# DI_DO.net
KiCad netlist of a schematic drawn in Altium Designer
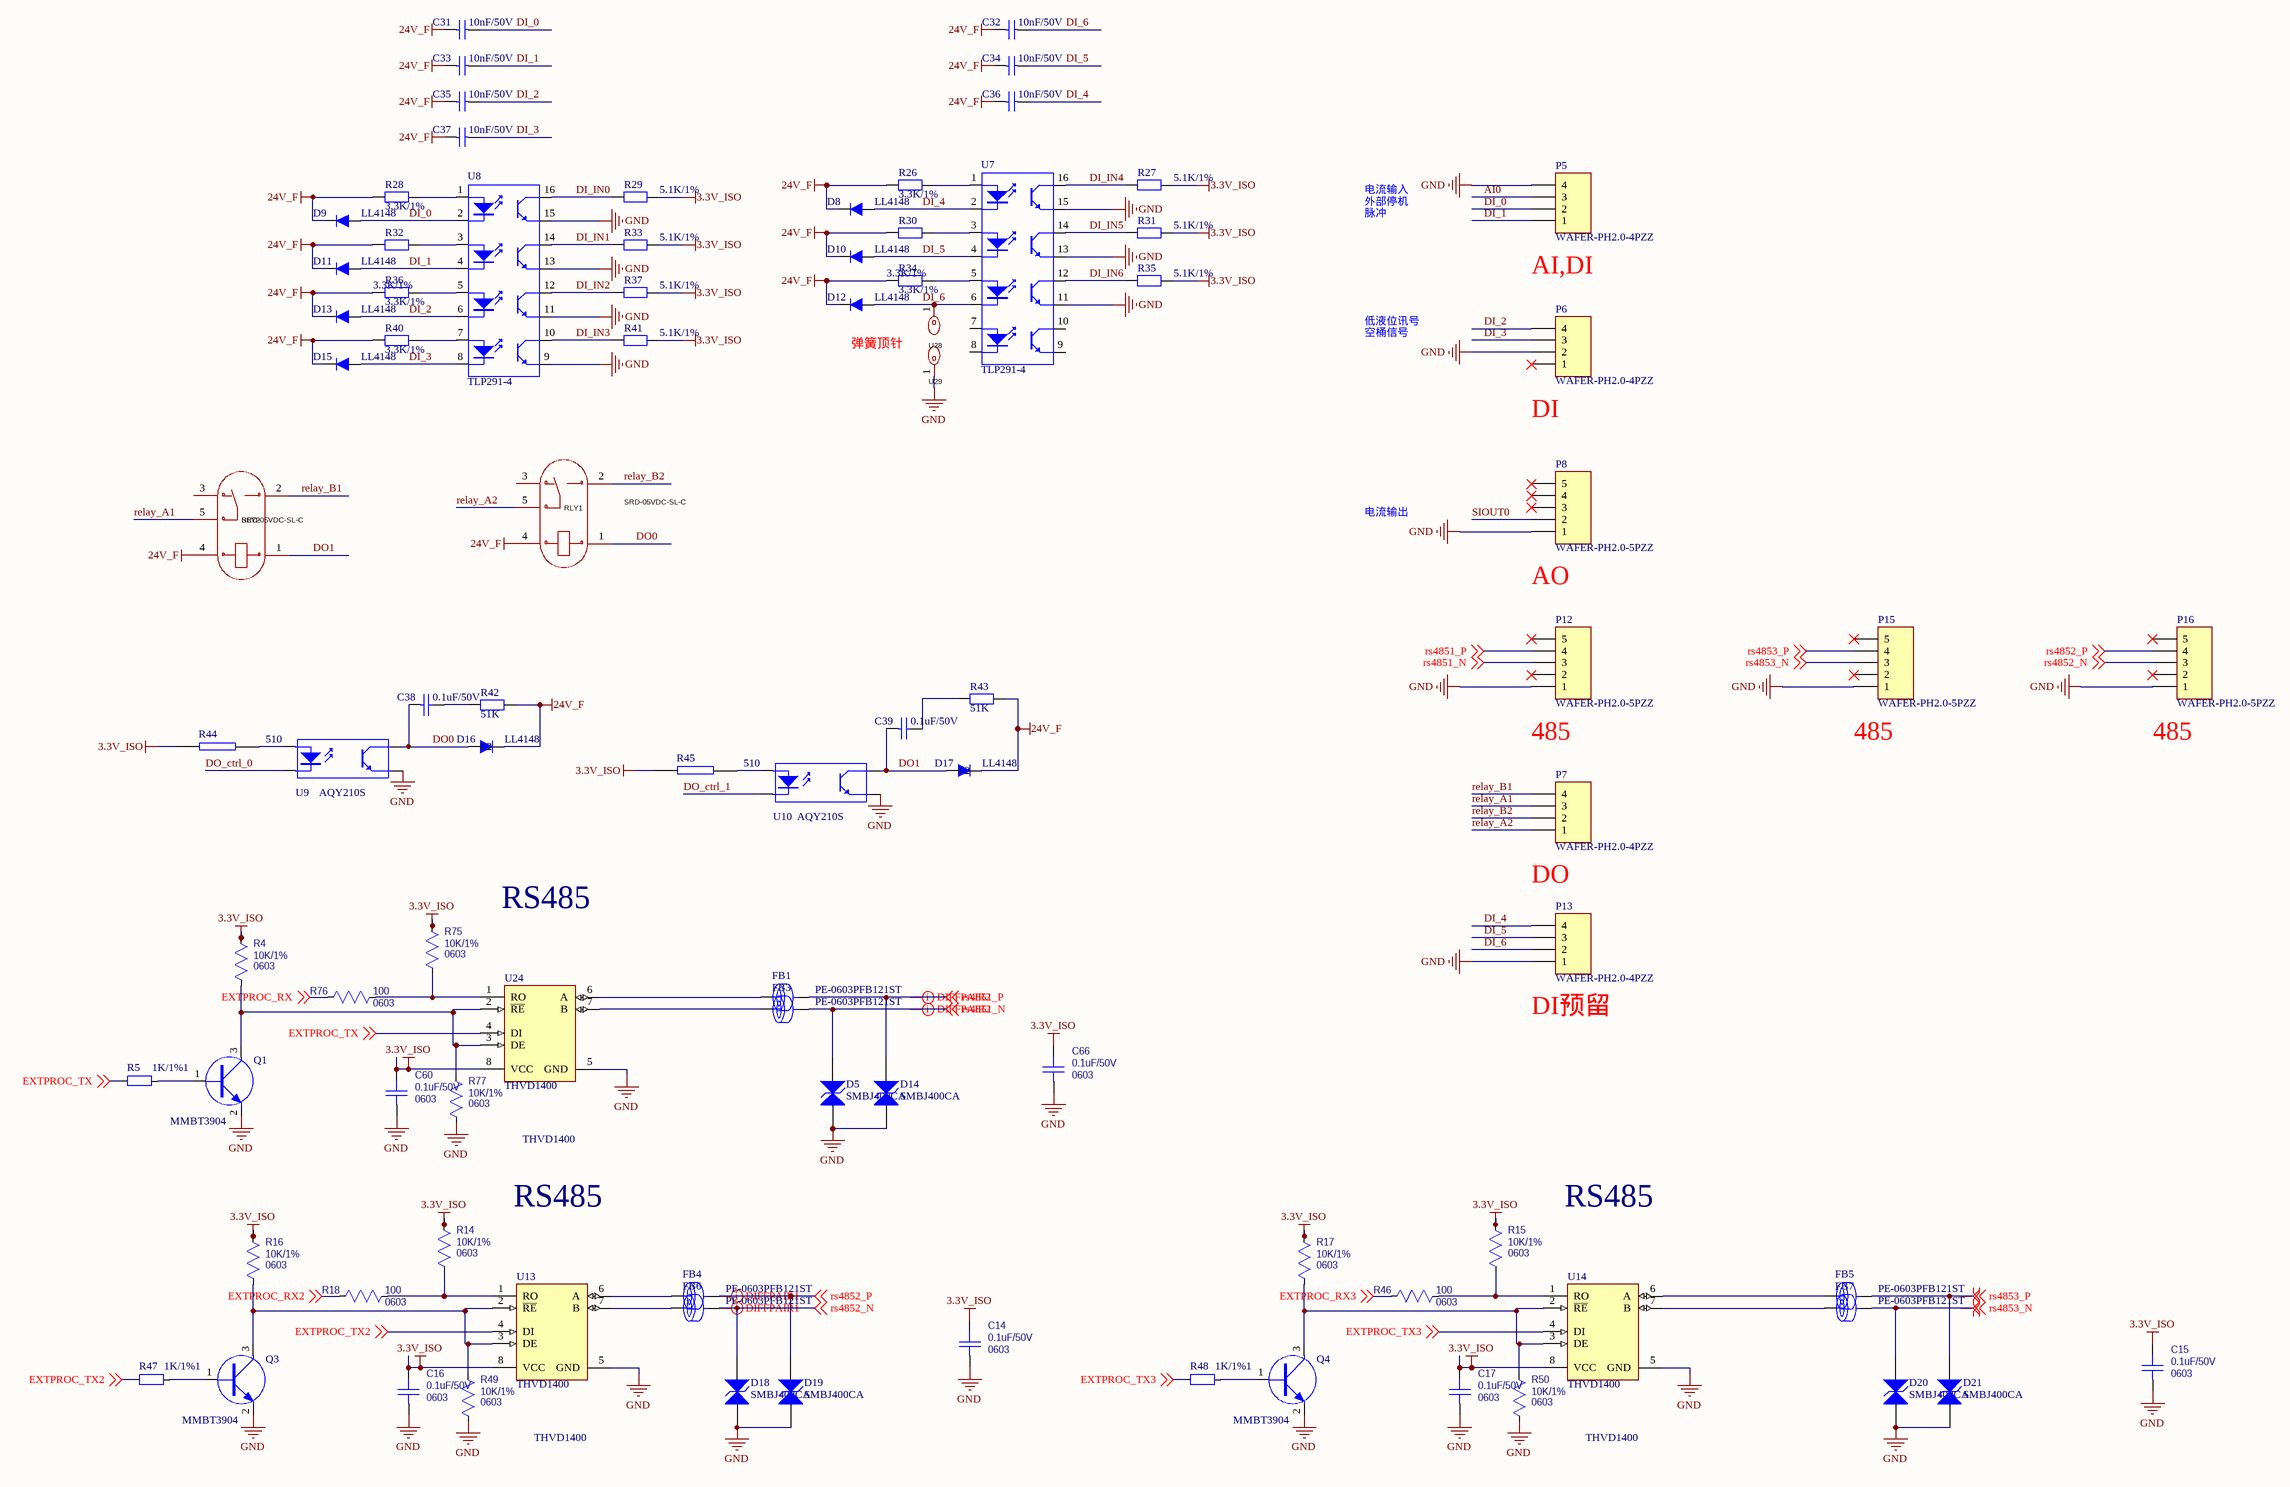
[diagram p0: DI_DO.SchDoc]

(export (version "E")
  (design (tool "Eeschema 10.0.6"))
  (components
    (comp (ref "C14")
      (value "0.1uF/50V")
      (footprint "0603C")
      (description "Capacitor, MLCC")
      (fields (field (name "PACKAGE") "0603"))
      (libsource (lib "Karl") (part "Capacitor_0603"))
    )
    (comp (ref "C15")
      (value "0.1uF/50V")
      (footprint "0603C")
      (description "Capacitor, MLCC")
      (fields (field (name "PACKAGE") "0603"))
      (libsource (lib "Karl") (part "Capacitor_0603"))
    )
    (comp (ref "C16")
      (value "0.1uF/50V")
      (footprint "0603C")
      (description "Capacitor, MLCC")
      (fields (field (name "PACKAGE") "0603"))
      (libsource (lib "Karl") (part "Capacitor_0603"))
    )
    (comp (ref "C17")
      (value "0.1uF/50V")
      (footprint "0603C")
      (description "Capacitor, MLCC")
      (fields (field (name "PACKAGE") "0603"))
      (libsource (lib "Karl") (part "Capacitor_0603"))
    )
    (comp (ref "C31")
      (value "10nF/50V")
      (footprint "0603C")
      (description "Capacitor")
      (libsource (lib "Miscellaneous Devices") (part "Cap"))
    )
    (comp (ref "C32")
      (value "10nF/50V")
      (footprint "0603C")
      (description "Capacitor")
      (libsource (lib "Miscellaneous Devices") (part "Cap"))
    )
    (comp (ref "C33")
      (value "10nF/50V")
      (footprint "0603C")
      (description "Capacitor")
      (libsource (lib "Miscellaneous Devices") (part "Cap"))
    )
    (comp (ref "C34")
      (value "10nF/50V")
      (footprint "0603C")
      (description "Capacitor")
      (libsource (lib "Miscellaneous Devices") (part "Cap"))
    )
    (comp (ref "C35")
      (value "10nF/50V")
      (footprint "0603C")
      (description "Capacitor")
      (libsource (lib "Miscellaneous Devices") (part "Cap"))
    )
    (comp (ref "C36")
      (value "10nF/50V")
      (footprint "0603C")
      (description "Capacitor")
      (libsource (lib "Miscellaneous Devices") (part "Cap"))
    )
    (comp (ref "C37")
      (value "10nF/50V")
      (footprint "0603C")
      (description "Capacitor")
      (libsource (lib "Miscellaneous Devices") (part "Cap"))
    )
    (comp (ref "C38")
      (value "0.1uF/50V")
      (footprint "0603C")
      (description "Capacitor")
      (libsource (lib "*") (part "CAP"))
    )
    (comp (ref "C39")
      (value "0.1uF/50V")
      (footprint "0603C")
      (description "Capacitor")
      (libsource (lib "*") (part "CAP"))
    )
    (comp (ref "C60")
      (value "0.1uF/50V")
      (footprint "0603C")
      (description "Capacitor, MLCC")
      (fields (field (name "PACKAGE") "0603"))
      (libsource (lib "Karl") (part "Capacitor_0603"))
    )
    (comp (ref "C66")
      (value "0.1uF/50V")
      (footprint "0603C")
      (description "Capacitor, MLCC")
      (fields (field (name "PACKAGE") "0603"))
      (libsource (lib "Karl") (part "Capacitor_0603"))
    )
    (comp (ref "D5")
      (value "SMBJ400CA")
      (footprint "SMB")
      (description "Transient Voltage Suppression Diode, 400 W, 33 V, -65 to 150 degC, 2-Pin SMD, RoHS, Tape and Reel")
      (libsource (lib "Bogen") (part "SMAJ12CA"))
    )
    (comp (ref "D8")
      (value "LL4148")
      (footprint "DO-213AB/LL34/MiniMELF")
      (description "VISHAY,LL4148,圆柱体MiniMELF100V/2A,ROHS")
      (libsource (lib "Device2018") (part "LL4148"))
    )
    (comp (ref "D9")
      (value "LL4148")
      (footprint "DO-213AB/LL34/MiniMELF")
      (description "VISHAY,LL4148,圆柱体MiniMELF100V/2A,ROHS")
      (libsource (lib "Device2018") (part "LL4148"))
    )
    (comp (ref "D10")
      (value "LL4148")
      (footprint "DO-213AB/LL34/MiniMELF")
      (description "VISHAY,LL4148,圆柱体MiniMELF100V/2A,ROHS")
      (libsource (lib "Device2018") (part "LL4148"))
    )
    (comp (ref "D11")
      (value "LL4148")
      (footprint "DO-213AB/LL34/MiniMELF")
      (description "VISHAY,LL4148,圆柱体MiniMELF100V/2A,ROHS")
      (libsource (lib "Device2018") (part "LL4148"))
    )
    (comp (ref "D12")
      (value "LL4148")
      (footprint "DO-213AB/LL34/MiniMELF")
      (description "VISHAY,LL4148,圆柱体MiniMELF100V/2A,ROHS")
      (libsource (lib "Device2018") (part "LL4148"))
    )
    (comp (ref "D13")
      (value "LL4148")
      (footprint "DO-213AB/LL34/MiniMELF")
      (description "VISHAY,LL4148,圆柱体MiniMELF100V/2A,ROHS")
      (libsource (lib "Device2018") (part "LL4148"))
    )
    (comp (ref "D14")
      (value "SMBJ400CA")
      (footprint "SMB")
      (description "Transient Voltage Suppression Diode, 400 W, 33 V, -65 to 150 degC, 2-Pin SMD, RoHS, Tape and Reel")
      (libsource (lib "Bogen") (part "SMAJ12CA"))
    )
    (comp (ref "D15")
      (value "LL4148")
      (footprint "DO-213AB/LL34/MiniMELF")
      (description "VISHAY,LL4148,圆柱体MiniMELF100V/2A,ROHS")
      (libsource (lib "Device2018") (part "LL4148"))
    )
    (comp (ref "D16")
      (value "LL4148")
      (footprint "DO-213AB/LL34/MiniMELF")
      (description "VISHAY,LL4148,圆柱体MiniMELF100V/2A,ROHS")
      (libsource (lib "") (part "LL4148_1"))
    )
    (comp (ref "D17")
      (value "LL4148")
      (footprint "DO-213AB/LL34/MiniMELF")
      (description "VISHAY,LL4148,圆柱体MiniMELF100V/2A,ROHS")
      (libsource (lib "") (part "LL4148_1"))
    )
    (comp (ref "D18")
      (value "SMBJ400CA")
      (footprint "SMB")
      (description "Transient Voltage Suppression Diode, 400 W, 33 V, -65 to 150 degC, 2-Pin SMD, RoHS, Tape and Reel")
      (libsource (lib "Bogen") (part "SMAJ12CA"))
    )
    (comp (ref "D19")
      (value "SMBJ400CA")
      (footprint "SMB")
      (description "Transient Voltage Suppression Diode, 400 W, 33 V, -65 to 150 degC, 2-Pin SMD, RoHS, Tape and Reel")
      (libsource (lib "Bogen") (part "SMAJ12CA"))
    )
    (comp (ref "D20")
      (value "SMBJ400CA")
      (footprint "SMB")
      (description "Transient Voltage Suppression Diode, 400 W, 33 V, -65 to 150 degC, 2-Pin SMD, RoHS, Tape and Reel")
      (libsource (lib "Bogen") (part "SMAJ12CA"))
    )
    (comp (ref "D21")
      (value "SMBJ400CA")
      (footprint "SMB")
      (description "Transient Voltage Suppression Diode, 400 W, 33 V, -65 to 150 degC, 2-Pin SMD, RoHS, Tape and Reel")
      (libsource (lib "Bogen") (part "SMAJ12CA"))
    )
    (comp (ref "FB1")
      (value "PE-0603PFB121ST")
      (footprint "FBC0603")
      (description "Ferrite Bead Chip")
      (libsource (lib "Karl") (part "FBC0603"))
    )
    (comp (ref "FB3")
      (value "PE-0603PFB121ST")
      (footprint "FBC0603")
      (description "Ferrite Bead Chip")
      (libsource (lib "Karl") (part "FBC0603"))
    )
    (comp (ref "FB4")
      (value "PE-0603PFB121ST")
      (footprint "FBC0603")
      (description "Ferrite Bead Chip")
      (libsource (lib "Karl") (part "FBC0603"))
    )
    (comp (ref "FB5")
      (value "PE-0603PFB121ST")
      (footprint "FBC0603")
      (description "Ferrite Bead Chip")
      (libsource (lib "Karl") (part "FBC0603"))
    )
    (comp (ref "FB6")
      (value "PE-0603PFB121ST")
      (footprint "FBC0603")
      (description "Ferrite Bead Chip")
      (libsource (lib "Karl") (part "FBC0603"))
    )
    (comp (ref "FB7")
      (value "PE-0603PFB121ST")
      (footprint "FBC0603")
      (description "Ferrite Bead Chip")
      (libsource (lib "Karl") (part "FBC0603"))
    )
    (comp (ref "P5")
      (value "WAFER-PH2.0-4PZZ")
      (footprint "CONN#PH2.0-4A")
      (description "Header, 4-Pin")
      (libsource (lib "Miscellaneous Connectors") (part "Header 4"))
    )
    (comp (ref "P6")
      (value "WAFER-PH2.0-4PZZ")
      (footprint "CONN#PH2.0-4A")
      (description "Header, 4-Pin")
      (libsource (lib "Miscellaneous Connectors") (part "Header 4"))
    )
    (comp (ref "P7")
      (value "WAFER-PH2.0-4PZZ")
      (footprint "CONN#PH2.0-4A")
      (description "Header, 4-Pin")
      (libsource (lib "Miscellaneous Connectors") (part "Header 4"))
    )
    (comp (ref "P8")
      (value "WAFER-PH2.0-5PZZ")
      (footprint "CONN#PH2.0-5A")
      (description "Header, 5-Pin")
      (libsource (lib "Miscellaneous Connectors") (part "Header 5"))
    )
    (comp (ref "P12")
      (value "WAFER-PH2.0-5PZZ")
      (footprint "CONN#PH2.0-5A")
      (description "Header, 5-Pin")
      (libsource (lib "Miscellaneous Connectors") (part "Header 5"))
    )
    (comp (ref "P13")
      (value "WAFER-PH2.0-4PZZ")
      (footprint "CONN#PH2.0-4A")
      (description "Header, 4-Pin")
      (libsource (lib "Miscellaneous Connectors") (part "Header 4"))
    )
    (comp (ref "P15")
      (value "WAFER-PH2.0-5PZZ")
      (footprint "CONN#PH2.0-5A")
      (description "Header, 5-Pin")
      (libsource (lib "Miscellaneous Connectors") (part "Header 5"))
    )
    (comp (ref "P16")
      (value "WAFER-PH2.0-5PZZ")
      (footprint "CONN#PH2.0-5A")
      (description "Header, 5-Pin")
      (libsource (lib "Miscellaneous Connectors") (part "Header 5"))
    )
    (comp (ref "Q1")
      (value "MMBT3904")
      (footprint "SOT23-3")
      (libsource (lib "CenLib") (part "NPN_MMBT3904"))
    )
    (comp (ref "Q3")
      (value "MMBT3904")
      (footprint "SOT23-3")
      (libsource (lib "CenLib") (part "NPN_MMBT3904"))
    )
    (comp (ref "Q4")
      (value "MMBT3904")
      (footprint "SOT23-3")
      (libsource (lib "CenLib") (part "NPN_MMBT3904"))
    )
    (comp (ref "R4")
      (value "10K/1%")
      (footprint "0603R")
      (description "Resistor, Standard")
      (fields (field (name "PACKAGE") "0603"))
      (libsource (lib "Karl") (part "Resistor_0603"))
    )
    (comp (ref "R5") (value "1K/1%1") (footprint "0603r") (libsource (lib "RC_M_D_00") (part "RES0603")))
    (comp (ref "R14")
      (value "10K/1%")
      (footprint "0603R")
      (description "Resistor, Standard")
      (fields (field (name "PACKAGE") "0603"))
      (libsource (lib "Karl") (part "Resistor_0603"))
    )
    (comp (ref "R15")
      (value "10K/1%")
      (footprint "0603R")
      (description "Resistor, Standard")
      (fields (field (name "PACKAGE") "0603"))
      (libsource (lib "Karl") (part "Resistor_0603"))
    )
    (comp (ref "R16")
      (value "10K/1%")
      (footprint "0603R")
      (description "Resistor, Standard")
      (fields (field (name "PACKAGE") "0603"))
      (libsource (lib "Karl") (part "Resistor_0603"))
    )
    (comp (ref "R17")
      (value "10K/1%")
      (footprint "0603R")
      (description "Resistor, Standard")
      (fields (field (name "PACKAGE") "0603"))
      (libsource (lib "Karl") (part "Resistor_0603"))
    )
    (comp (ref "R18")
      (value "100")
      (footprint "0603R")
      (description "Resistor, Standard")
      (fields (field (name "PACKAGE") "0603"))
      (libsource (lib "Karl") (part "Resistor_0603"))
    )
    (comp (ref "R26") (value "3.3K/1%") (footprint "0603R") (libsource (lib "") (part "Res0805M_1")))
    (comp (ref "R27") (value "5.1K/1%") (footprint "0603R") (libsource (lib "") (part "Res0805M_1")))
    (comp (ref "R28") (value "3.3K/1%") (footprint "0603R") (libsource (lib "") (part "Res0805M_1")))
    (comp (ref "R29") (value "5.1K/1%") (footprint "0603R") (libsource (lib "") (part "Res0805M_1")))
    (comp (ref "R30") (value "3.3K/1%") (footprint "0603R") (libsource (lib "") (part "Res0805M_1")))
    (comp (ref "R31") (value "5.1K/1%") (footprint "0603R") (libsource (lib "") (part "Res0805M_1")))
    (comp (ref "R32") (value "3.3K/1%") (footprint "0603R") (libsource (lib "") (part "Res0805M_1")))
    (comp (ref "R33") (value "5.1K/1%") (footprint "0603R") (libsource (lib "") (part "Res0805M_1")))
    (comp (ref "R34") (value "3.3K/1%") (footprint "0603R") (libsource (lib "") (part "Res0805M_1")))
    (comp (ref "R35") (value "5.1K/1%") (footprint "0603R") (libsource (lib "") (part "Res0805M_1")))
    (comp (ref "R36") (value "3.3K/1%") (footprint "0603R") (libsource (lib "") (part "Res0805M_1")))
    (comp (ref "R37") (value "5.1K/1%") (footprint "0603R") (libsource (lib "") (part "Res0805M_1")))
    (comp (ref "R40") (value "3.3K/1%") (footprint "0603R") (libsource (lib "") (part "Res0805M_1")))
    (comp (ref "R41") (value "5.1K/1%") (footprint "0603R") (libsource (lib "") (part "Res0805M_1")))
    (comp (ref "R42") (value "51K") (footprint "0603R") (libsource (lib "MQlibrary") (part "Res0805M")))
    (comp (ref "R43") (value "51K") (footprint "0603R") (libsource (lib "MQlibrary") (part "Res0805M")))
    (comp (ref "R44") (value "510") (footprint "0603R") (libsource (lib "*") (part "RES2")))
    (comp (ref "R45") (value "510") (footprint "0603R") (libsource (lib "*") (part "RES2")))
    (comp (ref "R46")
      (value "100")
      (footprint "0603R")
      (description "Resistor, Standard")
      (fields (field (name "PACKAGE") "0603"))
      (libsource (lib "Karl") (part "Resistor_0603"))
    )
    (comp (ref "R47") (value "1K/1%1") (footprint "0603r") (libsource (lib "RC_M_D_00") (part "RES0603")))
    (comp (ref "R48") (value "1K/1%1") (footprint "0603r") (libsource (lib "RC_M_D_00") (part "RES0603")))
    (comp (ref "R49")
      (value "10K/1%")
      (footprint "0603R")
      (description "Resistor, Standard")
      (fields (field (name "PACKAGE") "0603"))
      (libsource (lib "Karl") (part "Resistor_0603"))
    )
    (comp (ref "R50")
      (value "10K/1%")
      (footprint "0603R")
      (description "Resistor, Standard")
      (fields (field (name "PACKAGE") "0603"))
      (libsource (lib "Karl") (part "Resistor_0603"))
    )
    (comp (ref "R75")
      (value "10K/1%")
      (footprint "0603R")
      (description "Resistor, Standard")
      (fields (field (name "PACKAGE") "0603"))
      (libsource (lib "Karl") (part "Resistor_0603"))
    )
    (comp (ref "R76")
      (value "100")
      (footprint "0603R")
      (description "Resistor, Standard")
      (fields (field (name "PACKAGE") "0603"))
      (libsource (lib "Karl") (part "Resistor_0603"))
    )
    (comp (ref "R77")
      (value "10K/1%")
      (footprint "0603R")
      (description "Resistor, Standard")
      (fields (field (name "PACKAGE") "0603"))
      (libsource (lib "Karl") (part "Resistor_0603"))
    )
    (comp (ref "RLY1")
      (value "SRD-05VDC-SL-C")
      (footprint "RELAY-TH_SRD-XXVDC-XL-C")
      (libsource (lib "altium-import") (part "root_0_SRD-05VDC-SL-C_"))
    )
    (comp (ref "RLY2")
      (value "SRD-05VDC-SL-C")
      (footprint "RELAY-TH_SRD-XXVDC-XL-C")
      (libsource (lib "altium-import") (part "root_0_SRD-05VDC-SL-C_"))
    )
    (comp (ref "U7") (value "TLP291-4") (footprint "SOP16-T") (libsource (lib "DI16") (part "TLP281-4")))
    (comp (ref "U8") (value "TLP291-4") (footprint "SOP16-T") (libsource (lib "DI16") (part "TLP281-4")))
    (comp (ref "U9")
      (value "AQY210S")
      (footprint "sop4")
      (description "4-Pin Phototransistor Optocoupler")
      (libsource (lib "Miscellaneous Devices") (part "Optoisolator1"))
    )
    (comp (ref "U10")
      (value "AQY210S")
      (footprint "sop4")
      (description "4-Pin Phototransistor Optocoupler")
      (libsource (lib "Miscellaneous Devices") (part "Optoisolator1"))
    )
    (comp (ref "U13")
      (value "THVD1400")
      (footprint "MAXM-S8+4_M")
      (libsource (lib "Bogen") (part "MAX33071EASA+"))
    )
    (comp (ref "U14")
      (value "THVD1400")
      (footprint "MAXM-S8+4_M")
      (libsource (lib "Bogen") (part "MAX33071EASA+"))
    )
    (comp (ref "U24")
      (value "THVD1400")
      (footprint "MAXM-S8+4_M")
      (libsource (lib "Bogen") (part "MAX33071EASA+"))
    )
    (comp (ref "U28")
      (value "~")
      (footprint "CONN-SMD_YTC1P-3015-01")
      (libsource (lib "Flow_Pump") (part "YTC1P-3015-01"))
    )
    (comp (ref "U29")
      (value "~")
      (footprint "CONN-SMD_YTC1P-3015-01")
      (libsource (lib "Flow_Pump") (part "YTC1P-3015-01"))
    )
  )
  (nets
    (net (code "1") (name "/AI0") (class "Default")
      (node (ref "P5") (pin "3") (pinfunction "3_3") (pintype "passive"))
    )
    (net (code "2") (name "/DI_0") (class "Default")
      (node (ref "C31") (pin "2") (pinfunction "2_2") (pintype "passive"))
      (node (ref "D9") (pin "1") (pinfunction "2_1") (pintype "passive"))
      (node (ref "P5") (pin "2") (pinfunction "2_2") (pintype "passive"))
      (node (ref "U8") (pin "2") (pinfunction "K_2") (pintype "passive"))
    )
    (net (code "3") (name "/DI_1") (class "Default")
      (node (ref "C33") (pin "2") (pinfunction "2_2") (pintype "passive"))
      (node (ref "D11") (pin "1") (pinfunction "2_1") (pintype "passive"))
      (node (ref "P5") (pin "1") (pinfunction "1_1") (pintype "passive"))
      (node (ref "U8") (pin "4") (pinfunction "K_4") (pintype "passive"))
    )
    (net (code "4") (name "/DI_2") (class "Default")
      (node (ref "C35") (pin "2") (pinfunction "2_2") (pintype "passive"))
      (node (ref "D13") (pin "1") (pinfunction "2_1") (pintype "passive"))
      (node (ref "P6") (pin "4") (pinfunction "4_4") (pintype "passive"))
      (node (ref "U8") (pin "6") (pinfunction "K_6") (pintype "passive"))
    )
    (net (code "5") (name "/DI_3") (class "Default")
      (node (ref "C37") (pin "2") (pinfunction "2_2") (pintype "passive"))
      (node (ref "D15") (pin "1") (pinfunction "2_1") (pintype "passive"))
      (node (ref "P6") (pin "3") (pinfunction "3_3") (pintype "passive"))
      (node (ref "U8") (pin "8") (pinfunction "K_8") (pintype "passive"))
    )
    (net (code "6") (name "/DI_4") (class "Default")
      (node (ref "C36") (pin "2") (pinfunction "2_2") (pintype "passive"))
      (node (ref "D8") (pin "1") (pinfunction "2_1") (pintype "passive"))
      (node (ref "P13") (pin "4") (pinfunction "4_4") (pintype "passive"))
      (node (ref "U7") (pin "2") (pinfunction "K_2") (pintype "passive"))
    )
    (net (code "7") (name "/DI_5") (class "Default")
      (node (ref "C34") (pin "2") (pinfunction "2_2") (pintype "passive"))
      (node (ref "D10") (pin "1") (pinfunction "2_1") (pintype "passive"))
      (node (ref "P13") (pin "3") (pinfunction "3_3") (pintype "passive"))
      (node (ref "U7") (pin "4") (pinfunction "K_4") (pintype "passive"))
    )
    (net (code "8") (name "/DI_6") (class "Default")
      (node (ref "C32") (pin "2") (pinfunction "2_2") (pintype "passive"))
      (node (ref "D12") (pin "1") (pinfunction "2_1") (pintype "passive"))
      (node (ref "P13") (pin "2") (pinfunction "2_2") (pintype "passive"))
      (node (ref "U28") (pin "1") (pinfunction "1_1") (pintype "passive"))
      (node (ref "U7") (pin "6") (pinfunction "K_6") (pintype "passive"))
    )
    (net (code "9") (name "/DI_IN0") (class "Default")
      (node (ref "R29") (pin "2") (pinfunction "2_2") (pintype "passive"))
      (node (ref "U8") (pin "16") (pinfunction "C_16") (pintype "passive"))
    )
    (net (code "10") (name "/DI_IN1") (class "Default")
      (node (ref "R33") (pin "2") (pinfunction "2_2") (pintype "passive"))
      (node (ref "U8") (pin "14") (pinfunction "C_14") (pintype "passive"))
    )
    (net (code "11") (name "/DI_IN2") (class "Default")
      (node (ref "R37") (pin "2") (pinfunction "2_2") (pintype "passive"))
      (node (ref "U8") (pin "12") (pinfunction "C_12") (pintype "passive"))
    )
    (net (code "12") (name "/DI_IN3") (class "Default")
      (node (ref "R41") (pin "2") (pinfunction "2_2") (pintype "passive"))
      (node (ref "U8") (pin "10") (pinfunction "C_10") (pintype "passive"))
    )
    (net (code "13") (name "/DI_IN4") (class "Default")
      (node (ref "R27") (pin "2") (pinfunction "2_2") (pintype "passive"))
      (node (ref "U7") (pin "16") (pinfunction "C_16") (pintype "passive"))
    )
    (net (code "14") (name "/DI_IN5") (class "Default")
      (node (ref "R31") (pin "2") (pinfunction "2_2") (pintype "passive"))
      (node (ref "U7") (pin "14") (pinfunction "C_14") (pintype "passive"))
    )
    (net (code "15") (name "/DI_IN6") (class "Default")
      (node (ref "R35") (pin "2") (pinfunction "2_2") (pintype "passive"))
      (node (ref "U7") (pin "12") (pinfunction "C_12") (pintype "passive"))
    )
    (net (code "16") (name "/DO0") (class "Default")
      (node (ref "C38") (pin "1") (pinfunction "1_1") (pintype "passive"))
      (node (ref "D16") (pin "1") (pinfunction "2_1") (pintype "passive"))
      (node (ref "RLY1") (pin "1") (pinfunction "1_1") (pintype "passive"))
      (node (ref "U9") (pin "4") (pinfunction "C_4") (pintype "passive"))
    )
    (net (code "17") (name "/DO1") (class "Default")
      (node (ref "C39") (pin "1") (pinfunction "1_1") (pintype "passive"))
      (node (ref "D17") (pin "1") (pinfunction "2_1") (pintype "passive"))
      (node (ref "RLY2") (pin "1") (pinfunction "1_1") (pintype "passive"))
      (node (ref "U10") (pin "4") (pinfunction "C_4") (pintype "passive"))
    )
    (net (code "18") (name "/DO_ctrl_0") (class "Default")
      (node (ref "U9") (pin "2") (pinfunction "K_2") (pintype "passive"))
    )
    (net (code "19") (name "/DO_ctrl_1") (class "Default")
      (node (ref "U10") (pin "2") (pinfunction "K_2") (pintype "passive"))
    )
    (net (code "20") (name "/SIOUT0") (class "Default")
      (node (ref "P8") (pin "2") (pinfunction "2_2") (pintype "passive"))
    )
    (net (code "21") (name "/relay_A1") (class "Default")
      (node (ref "P7") (pin "3") (pinfunction "3_3") (pintype "passive"))
      (node (ref "RLY2") (pin "5") (pinfunction "5_5") (pintype "passive"))
    )
    (net (code "22") (name "/relay_A2") (class "Default")
      (node (ref "P7") (pin "1") (pinfunction "1_1") (pintype "passive"))
      (node (ref "RLY1") (pin "5") (pinfunction "5_5") (pintype "passive"))
    )
    (net (code "23") (name "/relay_B1") (class "Default")
      (node (ref "P7") (pin "4") (pinfunction "4_4") (pintype "passive"))
      (node (ref "RLY2") (pin "2") (pinfunction "2_2") (pintype "passive"))
    )
    (net (code "24") (name "/relay_B2") (class "Default")
      (node (ref "P7") (pin "2") (pinfunction "2_2") (pintype "passive"))
      (node (ref "RLY1") (pin "2") (pinfunction "2_2") (pintype "passive"))
    )
    (net (code "25") (name "3.3V_ISO") (class "Default")
      (node (ref "C14") (pin "1") (pinfunction "1_1") (pintype "passive"))
      (node (ref "C15") (pin "1") (pinfunction "1_1") (pintype "passive"))
      (node (ref "C16") (pin "1") (pinfunction "1_1") (pintype "passive"))
      (node (ref "C17") (pin "1") (pinfunction "1_1") (pintype "passive"))
      (node (ref "C60") (pin "1") (pinfunction "1_1") (pintype "passive"))
      (node (ref "C66") (pin "1") (pinfunction "1_1") (pintype "passive"))
      (node (ref "R14") (pin "2") (pinfunction "2_2") (pintype "passive"))
      (node (ref "R15") (pin "2") (pinfunction "2_2") (pintype "passive"))
      (node (ref "R16") (pin "2") (pinfunction "2_2") (pintype "passive"))
      (node (ref "R17") (pin "2") (pinfunction "2_2") (pintype "passive"))
      (node (ref "R27") (pin "1") (pinfunction "1_1") (pintype "passive"))
      (node (ref "R29") (pin "1") (pinfunction "1_1") (pintype "passive"))
      (node (ref "R31") (pin "1") (pinfunction "1_1") (pintype "passive"))
      (node (ref "R33") (pin "1") (pinfunction "1_1") (pintype "passive"))
      (node (ref "R35") (pin "1") (pinfunction "1_1") (pintype "passive"))
      (node (ref "R37") (pin "1") (pinfunction "1_1") (pintype "passive"))
      (node (ref "R4") (pin "2") (pinfunction "2_2") (pintype "passive"))
      (node (ref "R41") (pin "1") (pinfunction "1_1") (pintype "passive"))
      (node (ref "R44") (pin "2") (pinfunction "2_2") (pintype "passive"))
      (node (ref "R45") (pin "2") (pinfunction "2_2") (pintype "passive"))
      (node (ref "R75") (pin "2") (pinfunction "2_2") (pintype "passive"))
      (node (ref "U13") (pin "8") (pinfunction "VCC_8") (pintype "power_in"))
      (node (ref "U14") (pin "8") (pinfunction "VCC_8") (pintype "power_in"))
      (node (ref "U24") (pin "8") (pinfunction "VCC_8") (pintype "power_in"))
    )
    (net (code "26") (name "24V_F") (class "Default")
      (node (ref "C31") (pin "1") (pinfunction "1_1") (pintype "passive"))
      (node (ref "C32") (pin "1") (pinfunction "1_1") (pintype "passive"))
      (node (ref "C33") (pin "1") (pinfunction "1_1") (pintype "passive"))
      (node (ref "C34") (pin "1") (pinfunction "1_1") (pintype "passive"))
      (node (ref "C35") (pin "1") (pinfunction "1_1") (pintype "passive"))
      (node (ref "C36") (pin "1") (pinfunction "1_1") (pintype "passive"))
      (node (ref "C37") (pin "1") (pinfunction "1_1") (pintype "passive"))
      (node (ref "D10") (pin "2") (pinfunction "1_2") (pintype "passive"))
      (node (ref "D11") (pin "2") (pinfunction "1_2") (pintype "passive"))
      (node (ref "D12") (pin "2") (pinfunction "1_2") (pintype "passive"))
      (node (ref "D13") (pin "2") (pinfunction "1_2") (pintype "passive"))
      (node (ref "D15") (pin "2") (pinfunction "1_2") (pintype "passive"))
      (node (ref "D16") (pin "2") (pinfunction "1_2") (pintype "passive"))
      (node (ref "D17") (pin "2") (pinfunction "1_2") (pintype "passive"))
      (node (ref "D8") (pin "2") (pinfunction "1_2") (pintype "passive"))
      (node (ref "D9") (pin "2") (pinfunction "1_2") (pintype "passive"))
      (node (ref "R26") (pin "2") (pinfunction "2_2") (pintype "passive"))
      (node (ref "R28") (pin "2") (pinfunction "2_2") (pintype "passive"))
      (node (ref "R30") (pin "2") (pinfunction "2_2") (pintype "passive"))
      (node (ref "R32") (pin "2") (pinfunction "2_2") (pintype "passive"))
      (node (ref "R34") (pin "2") (pinfunction "2_2") (pintype "passive"))
      (node (ref "R36") (pin "2") (pinfunction "2_2") (pintype "passive"))
      (node (ref "R40") (pin "2") (pinfunction "2_2") (pintype "passive"))
      (node (ref "R42") (pin "2") (pinfunction "2_2") (pintype "passive"))
      (node (ref "R43") (pin "2") (pinfunction "2_2") (pintype "passive"))
      (node (ref "RLY1") (pin "4") (pinfunction "4_4") (pintype "passive"))
      (node (ref "RLY2") (pin "4") (pinfunction "4_4") (pintype "passive"))
    )
    (net (code "27") (name "EXTPROC_RX") (class "Default")
      (node (ref "R76") (pin "2") (pinfunction "2_2") (pintype "passive"))
    )
    (net (code "28") (name "EXTPROC_RX2") (class "Default")
      (node (ref "R18") (pin "2") (pinfunction "2_2") (pintype "passive"))
    )
    (net (code "29") (name "EXTPROC_RX3") (class "Default")
      (node (ref "R46") (pin "2") (pinfunction "2_2") (pintype "passive"))
    )
    (net (code "30") (name "EXTPROC_TX") (class "Default")
      (node (ref "R5") (pin "1") (pinfunction "1_1") (pintype "passive"))
      (node (ref "U24") (pin "4") (pinfunction "DI_4") (pintype "input"))
    )
    (net (code "31") (name "EXTPROC_TX2") (class "Default")
      (node (ref "R47") (pin "1") (pinfunction "1_1") (pintype "passive"))
      (node (ref "U13") (pin "4") (pinfunction "DI_4") (pintype "input"))
    )
    (net (code "32") (name "EXTPROC_TX3") (class "Default")
      (node (ref "R48") (pin "1") (pinfunction "1_1") (pintype "passive"))
      (node (ref "U14") (pin "4") (pinfunction "DI_4") (pintype "input"))
    )
    (net (code "33") (name "GND") (class "Default")
      (node (ref "C14") (pin "2") (pinfunction "2_2") (pintype "passive"))
      (node (ref "C15") (pin "2") (pinfunction "2_2") (pintype "passive"))
      (node (ref "C16") (pin "2") (pinfunction "2_2") (pintype "passive"))
      (node (ref "C17") (pin "2") (pinfunction "2_2") (pintype "passive"))
      (node (ref "C60") (pin "2") (pinfunction "2_2") (pintype "passive"))
      (node (ref "C66") (pin "2") (pinfunction "2_2") (pintype "passive"))
      (node (ref "D14") (pin "1") (pinfunction "A_1") (pintype "passive"))
      (node (ref "D18") (pin "1") (pinfunction "A_1") (pintype "passive"))
      (node (ref "D19") (pin "1") (pinfunction "A_1") (pintype "passive"))
      (node (ref "D20") (pin "1") (pinfunction "A_1") (pintype "passive"))
      (node (ref "D21") (pin "1") (pinfunction "A_1") (pintype "passive"))
      (node (ref "D5") (pin "1") (pinfunction "A_1") (pintype "passive"))
      (node (ref "P12") (pin "1") (pinfunction "1_1") (pintype "passive"))
      (node (ref "P13") (pin "1") (pinfunction "1_1") (pintype "passive"))
      (node (ref "P15") (pin "1") (pinfunction "1_1") (pintype "passive"))
      (node (ref "P16") (pin "1") (pinfunction "1_1") (pintype "passive"))
      (node (ref "P5") (pin "4") (pinfunction "4_4") (pintype "passive"))
      (node (ref "P6") (pin "2") (pinfunction "2_2") (pintype "passive"))
      (node (ref "P8") (pin "1") (pinfunction "1_1") (pintype "passive"))
      (node (ref "Q1") (pin "2") (pinfunction "E_2") (pintype "passive"))
      (node (ref "Q3") (pin "2") (pinfunction "E_2") (pintype "passive"))
      (node (ref "Q4") (pin "2") (pinfunction "E_2") (pintype "passive"))
      (node (ref "R49") (pin "1") (pinfunction "1_1") (pintype "passive"))
      (node (ref "R50") (pin "1") (pinfunction "1_1") (pintype "passive"))
      (node (ref "R77") (pin "1") (pinfunction "1_1") (pintype "passive"))
      (node (ref "U10") (pin "3") (pinfunction "E_3") (pintype "passive"))
      (node (ref "U13") (pin "5") (pinfunction "GND_5") (pintype "power_in"))
      (node (ref "U14") (pin "5") (pinfunction "GND_5") (pintype "power_in"))
      (node (ref "U24") (pin "5") (pinfunction "GND_5") (pintype "power_in"))
      (node (ref "U29") (pin "1") (pinfunction "1_1") (pintype "passive"))
      (node (ref "U7") (pin "11") (pinfunction "E_11") (pintype "passive"))
      (node (ref "U7") (pin "13") (pinfunction "E_13") (pintype "passive"))
      (node (ref "U7") (pin "15") (pinfunction "E_15") (pintype "passive"))
      (node (ref "U8") (pin "11") (pinfunction "E_11") (pintype "passive"))
      (node (ref "U8") (pin "13") (pinfunction "E_13") (pintype "passive"))
      (node (ref "U8") (pin "15") (pinfunction "E_15") (pintype "passive"))
      (node (ref "U8") (pin "9") (pinfunction "E_9") (pintype "passive"))
      (node (ref "U9") (pin "3") (pinfunction "E_3") (pintype "passive"))
    )
    (net (code "34") (name "Net-(C38-Pad2)") (class "Default")
      (node (ref "C38") (pin "2") (pinfunction "2_2") (pintype "passive"))
      (node (ref "R42") (pin "1") (pinfunction "1_1") (pintype "passive"))
    )
    (net (code "35") (name "Net-(C39-Pad2)") (class "Default")
      (node (ref "C39") (pin "2") (pinfunction "2_2") (pintype "passive"))
      (node (ref "R43") (pin "1") (pinfunction "1_1") (pintype "passive"))
    )
    (net (code "36") (name "Net-(Q1-B)") (class "Default")
      (node (ref "Q1") (pin "1") (pinfunction "B_1") (pintype "passive"))
      (node (ref "R5") (pin "2") (pinfunction "2_2") (pintype "passive"))
    )
    (net (code "37") (name "Net-(Q1-C)") (class "Default")
      (node (ref "Q1") (pin "3") (pinfunction "C_3") (pintype "passive"))
      (node (ref "R4") (pin "1") (pinfunction "1_1") (pintype "passive"))
      (node (ref "R77") (pin "2") (pinfunction "2_2") (pintype "passive"))
      (node (ref "U24") (pin "2") (pinfunction "~{RE}_2") (pintype "input"))
      (node (ref "U24") (pin "3") (pinfunction "DE_3") (pintype "input"))
    )
    (net (code "38") (name "Net-(Q3-B)") (class "Default")
      (node (ref "Q3") (pin "1") (pinfunction "B_1") (pintype "passive"))
      (node (ref "R47") (pin "2") (pinfunction "2_2") (pintype "passive"))
    )
    (net (code "39") (name "Net-(Q3-C)") (class "Default")
      (node (ref "Q3") (pin "3") (pinfunction "C_3") (pintype "passive"))
      (node (ref "R16") (pin "1") (pinfunction "1_1") (pintype "passive"))
      (node (ref "R49") (pin "2") (pinfunction "2_2") (pintype "passive"))
      (node (ref "U13") (pin "2") (pinfunction "~{RE}_2") (pintype "input"))
      (node (ref "U13") (pin "3") (pinfunction "DE_3") (pintype "input"))
    )
    (net (code "40") (name "Net-(Q4-B)") (class "Default")
      (node (ref "Q4") (pin "1") (pinfunction "B_1") (pintype "passive"))
      (node (ref "R48") (pin "2") (pinfunction "2_2") (pintype "passive"))
    )
    (net (code "41") (name "Net-(Q4-C)") (class "Default")
      (node (ref "Q4") (pin "3") (pinfunction "C_3") (pintype "passive"))
      (node (ref "R17") (pin "1") (pinfunction "1_1") (pintype "passive"))
      (node (ref "R50") (pin "2") (pinfunction "2_2") (pintype "passive"))
      (node (ref "U14") (pin "2") (pinfunction "~{RE}_2") (pintype "input"))
      (node (ref "U14") (pin "3") (pinfunction "DE_3") (pintype "input"))
    )
    (net (code "42") (name "Net-(R26-Pad1)") (class "Default")
      (node (ref "R26") (pin "1") (pinfunction "1_1") (pintype "passive"))
      (node (ref "U7") (pin "1") (pinfunction "A_1") (pintype "passive"))
    )
    (net (code "43") (name "Net-(R28-Pad1)") (class "Default")
      (node (ref "R28") (pin "1") (pinfunction "1_1") (pintype "passive"))
      (node (ref "U8") (pin "1") (pinfunction "A_1") (pintype "passive"))
    )
    (net (code "44") (name "Net-(R30-Pad1)") (class "Default")
      (node (ref "R30") (pin "1") (pinfunction "1_1") (pintype "passive"))
      (node (ref "U7") (pin "3") (pinfunction "A_3") (pintype "passive"))
    )
    (net (code "45") (name "Net-(R32-Pad1)") (class "Default")
      (node (ref "R32") (pin "1") (pinfunction "1_1") (pintype "passive"))
      (node (ref "U8") (pin "3") (pinfunction "A_3") (pintype "passive"))
    )
    (net (code "46") (name "Net-(R34-Pad1)") (class "Default")
      (node (ref "R34") (pin "1") (pinfunction "1_1") (pintype "passive"))
      (node (ref "U7") (pin "5") (pinfunction "A_5") (pintype "passive"))
    )
    (net (code "47") (name "Net-(R36-Pad1)") (class "Default")
      (node (ref "R36") (pin "1") (pinfunction "1_1") (pintype "passive"))
      (node (ref "U8") (pin "5") (pinfunction "A_5") (pintype "passive"))
    )
    (net (code "48") (name "Net-(R40-Pad1)") (class "Default")
      (node (ref "R40") (pin "1") (pinfunction "1_1") (pintype "passive"))
      (node (ref "U8") (pin "7") (pinfunction "A_7") (pintype "passive"))
    )
    (net (code "49") (name "Net-(U9-A)") (class "Default")
      (node (ref "R44") (pin "1") (pinfunction "1_1") (pintype "passive"))
      (node (ref "U9") (pin "1") (pinfunction "A_1") (pintype "passive"))
    )
    (net (code "50") (name "Net-(U10-A)") (class "Default")
      (node (ref "R45") (pin "1") (pinfunction "1_1") (pintype "passive"))
      (node (ref "U10") (pin "1") (pinfunction "A_1") (pintype "passive"))
    )
    (net (code "51") (name "Net-(U13-A)") (class "Default")
      (node (ref "FB4") (pin "1") (pinfunction "1_1") (pintype "passive"))
      (node (ref "U13") (pin "6") (pinfunction "A_6") (pintype "bidirectional"))
    )
    (net (code "52") (name "Net-(U13-B)") (class "Default")
      (node (ref "FB6") (pin "1") (pinfunction "1_1") (pintype "passive"))
      (node (ref "U13") (pin "7") (pinfunction "B_7") (pintype "bidirectional"))
    )
    (net (code "53") (name "Net-(U13-RO)") (class "Default")
      (node (ref "R14") (pin "1") (pinfunction "1_1") (pintype "passive"))
      (node (ref "R18") (pin "1") (pinfunction "1_1") (pintype "passive"))
      (node (ref "U13") (pin "1") (pinfunction "RO_1") (pintype "tri_state"))
    )
    (net (code "54") (name "Net-(U14-A)") (class "Default")
      (node (ref "FB5") (pin "1") (pinfunction "1_1") (pintype "passive"))
      (node (ref "U14") (pin "6") (pinfunction "A_6") (pintype "bidirectional"))
    )
    (net (code "55") (name "Net-(U14-B)") (class "Default")
      (node (ref "FB7") (pin "1") (pinfunction "1_1") (pintype "passive"))
      (node (ref "U14") (pin "7") (pinfunction "B_7") (pintype "bidirectional"))
    )
    (net (code "56") (name "Net-(U14-RO)") (class "Default")
      (node (ref "R15") (pin "1") (pinfunction "1_1") (pintype "passive"))
      (node (ref "R46") (pin "1") (pinfunction "1_1") (pintype "passive"))
      (node (ref "U14") (pin "1") (pinfunction "RO_1") (pintype "tri_state"))
    )
    (net (code "57") (name "Net-(U24-A)") (class "Default")
      (node (ref "FB1") (pin "1") (pinfunction "1_1") (pintype "passive"))
      (node (ref "U24") (pin "6") (pinfunction "A_6") (pintype "bidirectional"))
    )
    (net (code "58") (name "Net-(U24-B)") (class "Default")
      (node (ref "FB3") (pin "1") (pinfunction "1_1") (pintype "passive"))
      (node (ref "U24") (pin "7") (pinfunction "B_7") (pintype "bidirectional"))
    )
    (net (code "59") (name "Net-(U24-RO)") (class "Default")
      (node (ref "R75") (pin "1") (pinfunction "1_1") (pintype "passive"))
      (node (ref "R76") (pin "1") (pinfunction "1_1") (pintype "passive"))
      (node (ref "U24") (pin "1") (pinfunction "RO_1") (pintype "tri_state"))
    )
    (net (code "60") (name "rs4851_N") (class "Default")
      (node (ref "D5") (pin "2") (pinfunction "A_2") (pintype "passive"))
      (node (ref "FB3") (pin "2") (pinfunction "2_2") (pintype "passive"))
      (node (ref "P12") (pin "3") (pinfunction "3_3") (pintype "passive"))
    )
    (net (code "61") (name "rs4851_P") (class "Default")
      (node (ref "D14") (pin "2") (pinfunction "A_2") (pintype "passive"))
      (node (ref "FB1") (pin "2") (pinfunction "2_2") (pintype "passive"))
      (node (ref "P12") (pin "4") (pinfunction "4_4") (pintype "passive"))
    )
    (net (code "62") (name "rs4852_N") (class "Default")
      (node (ref "D18") (pin "2") (pinfunction "A_2") (pintype "passive"))
      (node (ref "FB6") (pin "2") (pinfunction "2_2") (pintype "passive"))
      (node (ref "P16") (pin "3") (pinfunction "3_3") (pintype "passive"))
    )
    (net (code "63") (name "rs4852_P") (class "Default")
      (node (ref "D19") (pin "2") (pinfunction "A_2") (pintype "passive"))
      (node (ref "FB4") (pin "2") (pinfunction "2_2") (pintype "passive"))
      (node (ref "P16") (pin "4") (pinfunction "4_4") (pintype "passive"))
    )
    (net (code "64") (name "rs4853_N") (class "Default")
      (node (ref "D20") (pin "2") (pinfunction "A_2") (pintype "passive"))
      (node (ref "FB7") (pin "2") (pinfunction "2_2") (pintype "passive"))
      (node (ref "P15") (pin "3") (pinfunction "3_3") (pintype "passive"))
    )
    (net (code "65") (name "rs4853_P") (class "Default")
      (node (ref "D21") (pin "2") (pinfunction "A_2") (pintype "passive"))
      (node (ref "FB5") (pin "2") (pinfunction "2_2") (pintype "passive"))
      (node (ref "P15") (pin "4") (pinfunction "4_4") (pintype "passive"))
    )
    (net (code "66") (name "unconnected-(P6-Pad1)") (class "Default")
      (node (ref "P6") (pin "1") (pinfunction "1_1") (pintype "passive+no_connect"))
    )
    (net (code "67") (name "unconnected-(P8-Pad3)") (class "Default")
      (node (ref "P8") (pin "3") (pinfunction "3_3") (pintype "passive+no_connect"))
    )
    (net (code "68") (name "unconnected-(P8-Pad4)") (class "Default")
      (node (ref "P8") (pin "4") (pinfunction "4_4") (pintype "passive+no_connect"))
    )
    (net (code "69") (name "unconnected-(P8-Pad5)") (class "Default")
      (node (ref "P8") (pin "5") (pinfunction "5_5") (pintype "passive+no_connect"))
    )
    (net (code "70") (name "unconnected-(P12-Pad2)") (class "Default")
      (node (ref "P12") (pin "2") (pinfunction "2_2") (pintype "passive+no_connect"))
    )
    (net (code "71") (name "unconnected-(P12-Pad5)") (class "Default")
      (node (ref "P12") (pin "5") (pinfunction "5_5") (pintype "passive+no_connect"))
    )
    (net (code "72") (name "unconnected-(P15-Pad2)") (class "Default")
      (node (ref "P15") (pin "2") (pinfunction "2_2") (pintype "passive+no_connect"))
    )
    (net (code "73") (name "unconnected-(P15-Pad5)") (class "Default")
      (node (ref "P15") (pin "5") (pinfunction "5_5") (pintype "passive+no_connect"))
    )
    (net (code "74") (name "unconnected-(P16-Pad2)") (class "Default")
      (node (ref "P16") (pin "2") (pinfunction "2_2") (pintype "passive+no_connect"))
    )
    (net (code "75") (name "unconnected-(P16-Pad5)") (class "Default")
      (node (ref "P16") (pin "5") (pinfunction "5_5") (pintype "passive+no_connect"))
    )
    (net (code "76") (name "unconnected-(RLY1-Pad3)") (class "Default")
      (node (ref "RLY1") (pin "3") (pinfunction "3_3") (pintype "passive"))
    )
    (net (code "77") (name "unconnected-(RLY2-Pad3)") (class "Default")
      (node (ref "RLY2") (pin "3") (pinfunction "3_3") (pintype "passive"))
    )
    (net (code "78") (name "unconnected-(U7-A-Pad7)") (class "Default")
      (node (ref "U7") (pin "7") (pinfunction "A_7") (pintype "passive"))
    )
    (net (code "79") (name "unconnected-(U7-C-Pad10)") (class "Default")
      (node (ref "U7") (pin "10") (pinfunction "C_10") (pintype "passive"))
    )
    (net (code "80") (name "unconnected-(U7-E-Pad9)") (class "Default")
      (node (ref "U7") (pin "9") (pinfunction "E_9") (pintype "passive"))
    )
    (net (code "81") (name "unconnected-(U7-K-Pad8)") (class "Default")
      (node (ref "U7") (pin "8") (pinfunction "K_8") (pintype "passive"))
    )
  )
)
